# Power.net
KiCad netlist of a schematic drawn in Altium Designer
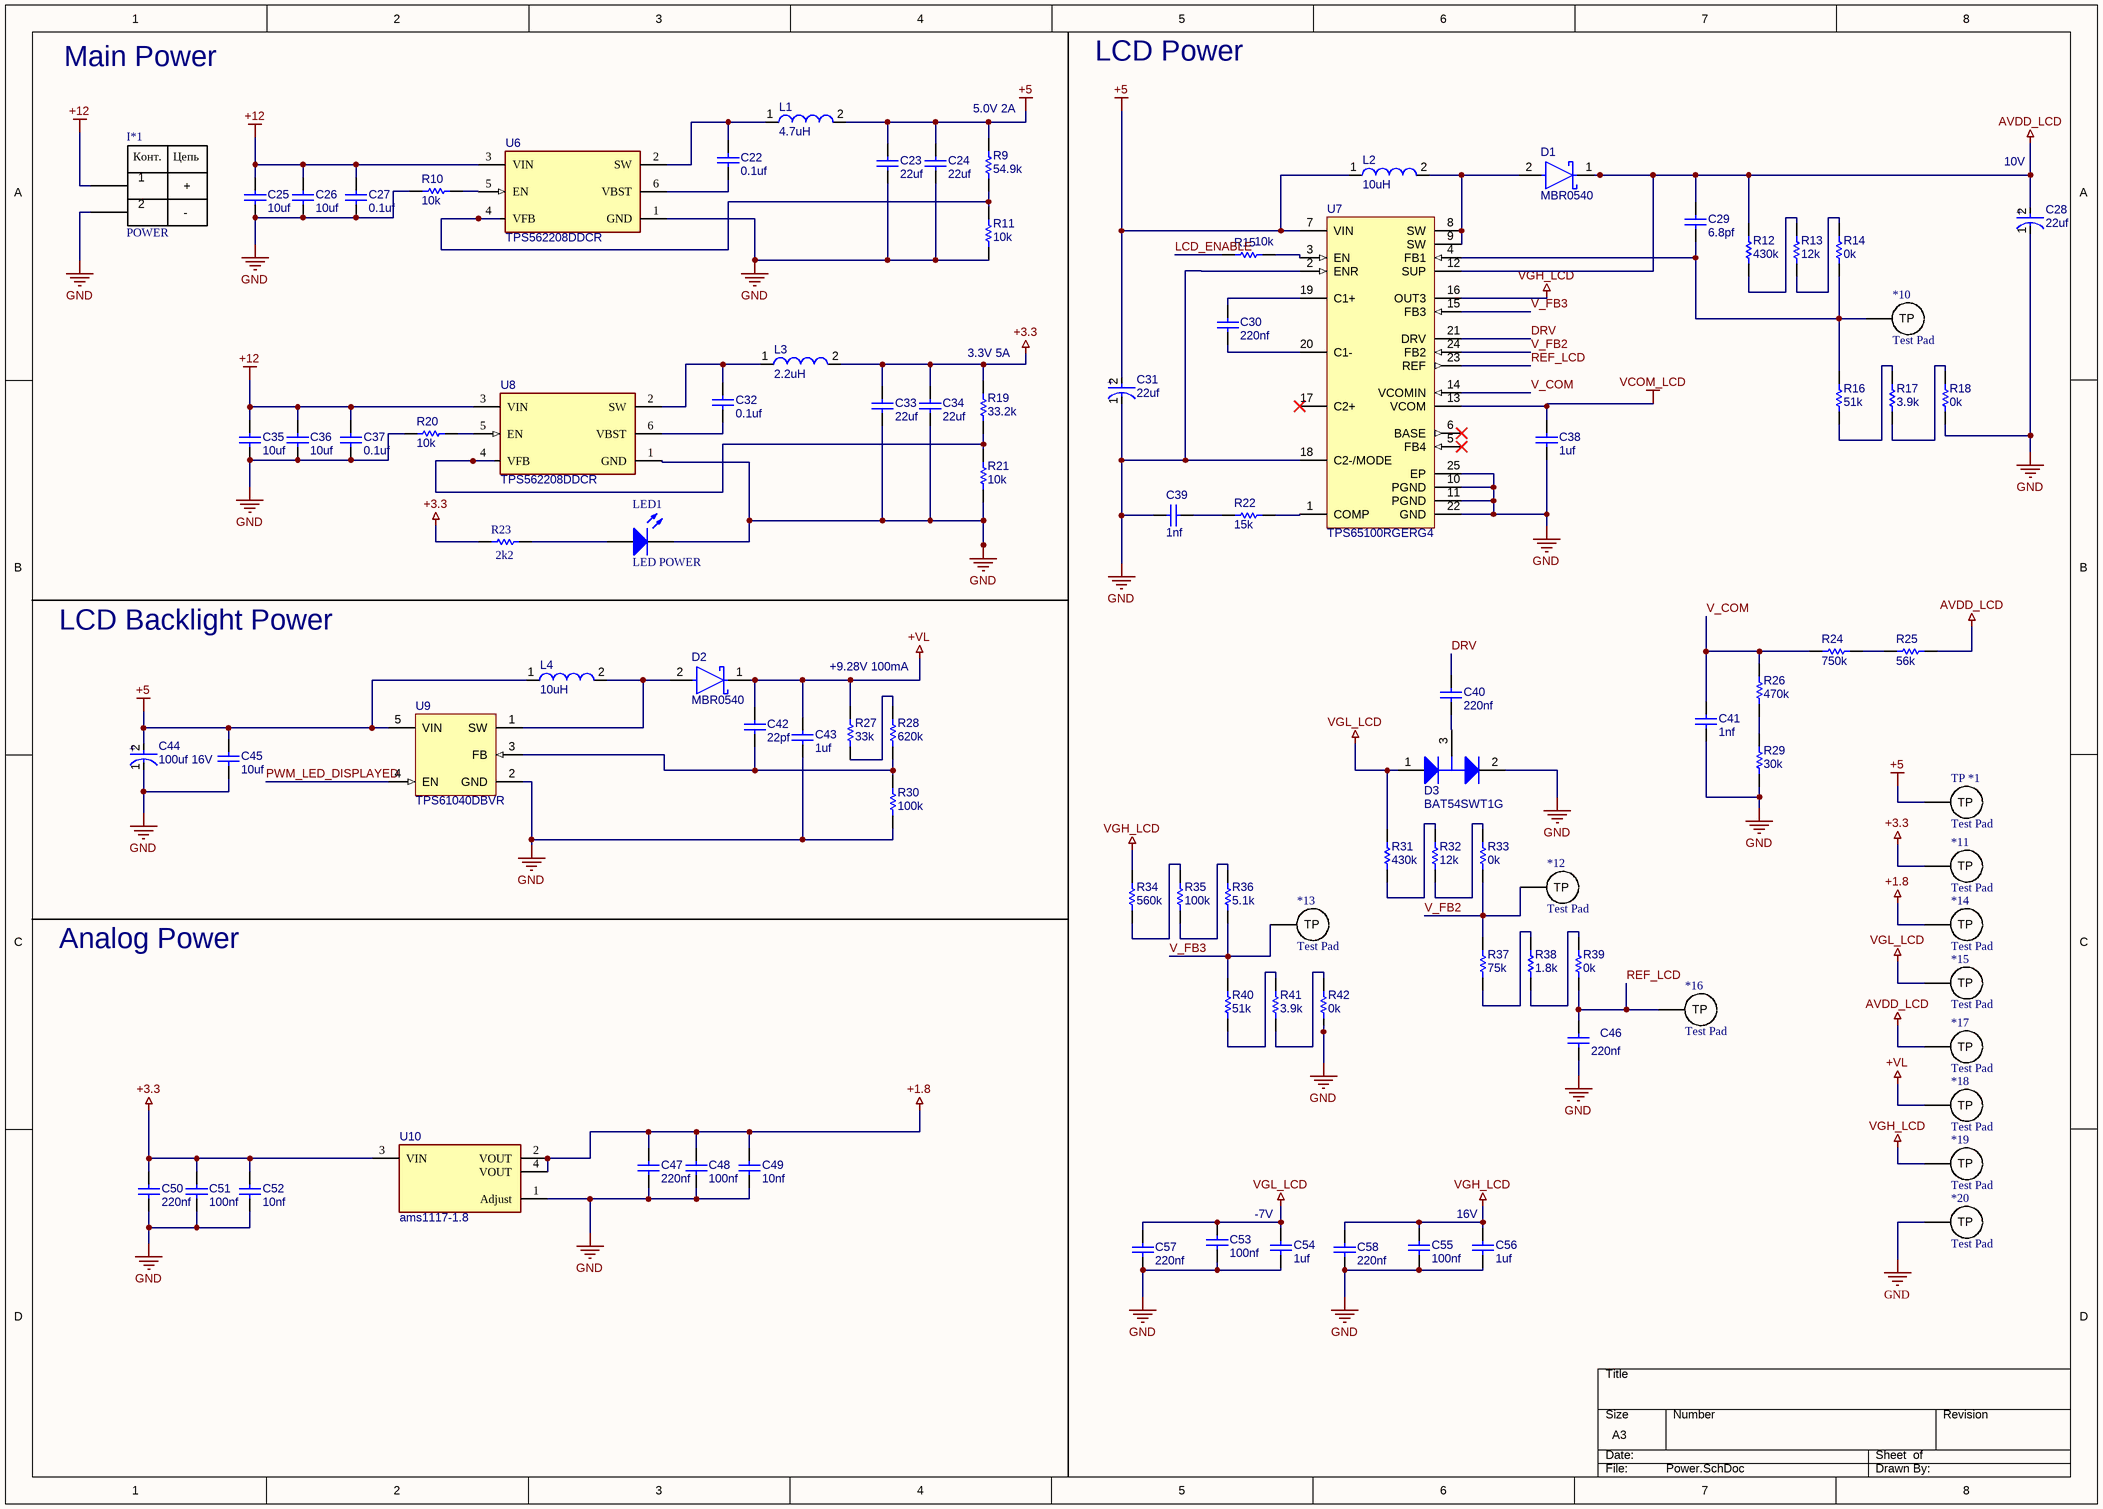
[diagram p0: Power.SchDoc]

(export (version "E")
  (design (tool "Eeschema 10.0.6"))
  (components
    (comp (ref "*10")
      (value "Test Pad")
      (footprint "Test Pad")
      (libsource (lib "Test Pad") (part "Test Pad"))
    )
    (comp (ref "*11")
      (value "Test Pad")
      (footprint "Test Pad")
      (libsource (lib "Test Pad") (part "Test Pad"))
    )
    (comp (ref "*12")
      (value "Test Pad")
      (footprint "Test Pad")
      (libsource (lib "Test Pad") (part "Test Pad"))
    )
    (comp (ref "*13")
      (value "Test Pad")
      (footprint "Test Pad")
      (libsource (lib "Test Pad") (part "Test Pad"))
    )
    (comp (ref "*14")
      (value "Test Pad")
      (footprint "Test Pad")
      (libsource (lib "Test Pad") (part "Test Pad"))
    )
    (comp (ref "*15")
      (value "Test Pad")
      (footprint "Test Pad")
      (libsource (lib "Test Pad") (part "Test Pad"))
    )
    (comp (ref "*16")
      (value "Test Pad")
      (footprint "Test Pad")
      (libsource (lib "Test Pad") (part "Test Pad"))
    )
    (comp (ref "*17")
      (value "Test Pad")
      (footprint "Test Pad")
      (libsource (lib "Test Pad") (part "Test Pad"))
    )
    (comp (ref "*18")
      (value "Test Pad")
      (footprint "Test Pad")
      (libsource (lib "Test Pad") (part "Test Pad"))
    )
    (comp (ref "*19")
      (value "Test Pad")
      (footprint "Test Pad")
      (libsource (lib "Test Pad") (part "Test Pad"))
    )
    (comp (ref "*20")
      (value "Test Pad")
      (footprint "Test Pad")
      (libsource (lib "Test Pad") (part "Test Pad"))
    )
    (comp (ref "C22")
      (value "0.1uf")
      (footprint "CAPC2013X70X45NL10T25")
      (fields (field (name "PART NUMBER") "GRM216R61E105KA12D") (field (name "MANUFACTURER") "Murata"))
      (libsource (lib "Altium Content Vault") (part "CAP"))
    )
    (comp (ref "C23")
      (value "22uf")
      (footprint "CAPC2013X70X45NL10T25")
      (fields (field (name "PART NUMBER") "GRM216R61E105KA12D") (field (name "MANUFACTURER") "Murata"))
      (libsource (lib "Altium Content Vault") (part "CAP"))
    )
    (comp (ref "C24")
      (value "22uf")
      (footprint "CAPC2013X70X45NL10T25")
      (fields (field (name "PART NUMBER") "GRM216R61E105KA12D") (field (name "MANUFACTURER") "Murata"))
      (libsource (lib "Altium Content Vault") (part "CAP"))
    )
    (comp (ref "C25")
      (value "10uf")
      (footprint "CAPC2013X70X45NL10T25")
      (fields (field (name "PART NUMBER") "GRM216R61E105KA12D") (field (name "MANUFACTURER") "Murata"))
      (libsource (lib "Altium Content Vault") (part "CAP"))
    )
    (comp (ref "C26")
      (value "10uf")
      (footprint "CAPC2013X70X45NL10T25")
      (fields (field (name "PART NUMBER") "GRM216R61E105KA12D") (field (name "MANUFACTURER") "Murata"))
      (libsource (lib "Altium Content Vault") (part "CAP"))
    )
    (comp (ref "C27")
      (value "0.1uf")
      (footprint "CAPC2013X70X45NL10T25")
      (fields (field (name "PART NUMBER") "GRM216R61E105KA12D") (field (name "MANUFACTURER") "Murata"))
      (libsource (lib "Altium Content Vault") (part "CAP"))
    )
    (comp (ref "C28")
      (value "22uf")
      (footprint "FP-TAJD-MFG")
      (description "22uF 16V  ±20% 1.1Ω 2917  SMD Tantalum Capacitor")
      (fields (field (name "TOLERANCE") "20%"))
      (libsource (lib "Altium Content Vault") (part "a00bbbee19879c290e62620ae7e47b1"))
    )
    (comp (ref "C29")
      (value "6.8pf")
      (footprint "CAPC2013X70X45NL10T25")
      (fields (field (name "PART NUMBER") "GRM216R61E105KA12D") (field (name "MANUFACTURER") "Murata"))
      (libsource (lib "Altium Content Vault") (part "CAP"))
    )
    (comp (ref "C30")
      (value "220nf")
      (footprint "CAPC2013X70X45NL10T25")
      (fields (field (name "PART NUMBER") "GRM216R61E105KA12D") (field (name "MANUFACTURER") "Murata"))
      (libsource (lib "Altium Content Vault") (part "CAP"))
    )
    (comp (ref "C31")
      (value "22uf")
      (footprint "FP-TAJD-MFG")
      (description "22uF 16V  ±20% 1.1Ω 2917  SMD Tantalum Capacitor")
      (fields (field (name "TOLERANCE") "20%"))
      (libsource (lib "Altium Content Vault") (part "a00bbbee19879c290e62620ae7e47b1"))
    )
    (comp (ref "C32")
      (value "0.1uf")
      (footprint "CAPC2013X70X45NL10T25")
      (fields (field (name "PART NUMBER") "GRM216R61E105KA12D") (field (name "MANUFACTURER") "Murata"))
      (libsource (lib "Altium Content Vault") (part "CAP"))
    )
    (comp (ref "C33")
      (value "22uf")
      (footprint "CAPC2013X70X45NL10T25")
      (fields (field (name "PART NUMBER") "GRM216R61E105KA12D") (field (name "MANUFACTURER") "Murata"))
      (libsource (lib "Altium Content Vault") (part "CAP"))
    )
    (comp (ref "C34")
      (value "22uf")
      (footprint "CAPC2013X70X45NL10T25")
      (fields (field (name "PART NUMBER") "GRM216R61E105KA12D") (field (name "MANUFACTURER") "Murata"))
      (libsource (lib "Altium Content Vault") (part "CAP"))
    )
    (comp (ref "C35")
      (value "10uf")
      (footprint "CAPC2013X70X45NL10T25")
      (fields (field (name "PART NUMBER") "GRM216R61E105KA12D") (field (name "MANUFACTURER") "Murata"))
      (libsource (lib "Altium Content Vault") (part "CAP"))
    )
    (comp (ref "C36")
      (value "10uf")
      (footprint "CAPC2013X70X45NL10T25")
      (fields (field (name "PART NUMBER") "GRM216R61E105KA12D") (field (name "MANUFACTURER") "Murata"))
      (libsource (lib "Altium Content Vault") (part "CAP"))
    )
    (comp (ref "C37")
      (value "0.1uf")
      (footprint "CAPC2013X70X45NL10T25")
      (fields (field (name "PART NUMBER") "GRM216R61E105KA12D") (field (name "MANUFACTURER") "Murata"))
      (libsource (lib "Altium Content Vault") (part "CAP"))
    )
    (comp (ref "C38")
      (value "1uf")
      (footprint "CAPC2013X70X45NL10T25")
      (fields (field (name "PART NUMBER") "GRM216R61E105KA12D") (field (name "MANUFACTURER") "Murata"))
      (libsource (lib "Altium Content Vault") (part "CAP"))
    )
    (comp (ref "C39")
      (value "1nf")
      (footprint "CAPC2013X70X45NL10T25")
      (fields (field (name "PART NUMBER") "GRM216R61E105KA12D") (field (name "MANUFACTURER") "Murata"))
      (libsource (lib "Altium Content Vault") (part "CAP"))
    )
    (comp (ref "C40")
      (value "220nf")
      (footprint "CAPC2013X70X45NL10T25")
      (fields (field (name "PART NUMBER") "GRM216R61E105KA12D") (field (name "MANUFACTURER") "Murata"))
      (libsource (lib "Altium Content Vault") (part "CAP"))
    )
    (comp (ref "C41")
      (value "1nf")
      (footprint "CAPC2013X70X45NL10T25")
      (fields (field (name "PART NUMBER") "GRM216R61E105KA12D") (field (name "MANUFACTURER") "Murata"))
      (libsource (lib "Altium Content Vault") (part "CAP"))
    )
    (comp (ref "C42")
      (value "22pf")
      (footprint "CAPC2013X70X45NL10T25")
      (fields (field (name "PART NUMBER") "GRM216R61E105KA12D") (field (name "MANUFACTURER") "Murata"))
      (libsource (lib "Altium Content Vault") (part "CAP"))
    )
    (comp (ref "C43")
      (value "1uf")
      (footprint "CAPC2013X70X45NL10T25")
      (fields (field (name "PART NUMBER") "GRM216R61E105KA12D") (field (name "MANUFACTURER") "Murata"))
      (libsource (lib "Altium Content Vault") (part "CAP"))
    )
    (comp (ref "C44")
      (value "100uf 16V")
      (footprint "FP-T491D107K016AT-MFG")
      (description "CAP TANT 100UF 10% 16V 2917")
      (fields (field (name "TOLERANCE") "10%") (field (name "VOLTAGE") "16V"))
      (libsource (lib "Altium Content Vault") (part "cf48714ba7e38822c1575c7ec0b6d1f"))
    )
    (comp (ref "C45")
      (value "10uf")
      (footprint "CAPC2013X70X45NL10T25")
      (fields (field (name "PART NUMBER") "GRM216R61E105KA12D") (field (name "MANUFACTURER") "Murata"))
      (libsource (lib "Altium Content Vault") (part "CAP"))
    )
    (comp (ref "C46")
      (value "220nf")
      (footprint "CAPC2013X70X45NL10T25")
      (fields (field (name "PART NUMBER") "GRM216R61E105KA12D") (field (name "MANUFACTURER") "Murata"))
      (libsource (lib "Altium Content Vault") (part "CAP"))
    )
    (comp (ref "C47")
      (value "220nf")
      (footprint "CAPC2013X70X45NL10T25")
      (fields (field (name "PART NUMBER") "GRM216R61E105KA12D") (field (name "MANUFACTURER") "Murata"))
      (libsource (lib "Altium Content Vault") (part "CAP"))
    )
    (comp (ref "C48")
      (value "100nf")
      (footprint "CAPC2013X70X45NL10T25")
      (fields (field (name "PART NUMBER") "GRM216R61E105KA12D") (field (name "MANUFACTURER") "Murata"))
      (libsource (lib "Altium Content Vault") (part "CAP"))
    )
    (comp (ref "C49")
      (value "10nf")
      (footprint "CAPC2013X70X45NL10T25")
      (fields (field (name "PART NUMBER") "GRM216R61E105KA12D") (field (name "MANUFACTURER") "Murata"))
      (libsource (lib "Altium Content Vault") (part "CAP"))
    )
    (comp (ref "C50")
      (value "220nf")
      (footprint "CAPC2013X70X45NL10T25")
      (fields (field (name "PART NUMBER") "GRM216R61E105KA12D") (field (name "MANUFACTURER") "Murata"))
      (libsource (lib "Altium Content Vault") (part "CAP"))
    )
    (comp (ref "C51")
      (value "100nf")
      (footprint "CAPC2013X70X45NL10T25")
      (fields (field (name "PART NUMBER") "GRM216R61E105KA12D") (field (name "MANUFACTURER") "Murata"))
      (libsource (lib "Altium Content Vault") (part "CAP"))
    )
    (comp (ref "C52")
      (value "10nf")
      (footprint "CAPC2013X70X45NL10T25")
      (fields (field (name "PART NUMBER") "GRM216R61E105KA12D") (field (name "MANUFACTURER") "Murata"))
      (libsource (lib "Altium Content Vault") (part "CAP"))
    )
    (comp (ref "C53")
      (value "100nf")
      (footprint "CAPC2013X70X45NL10T25")
      (fields (field (name "PART NUMBER") "GRM216R61E105KA12D") (field (name "MANUFACTURER") "Murata"))
      (libsource (lib "Altium Content Vault") (part "CAP"))
    )
    (comp (ref "C54")
      (value "1uf")
      (footprint "CAPC2013X70X45NL10T25")
      (fields (field (name "PART NUMBER") "GRM216R61E105KA12D") (field (name "MANUFACTURER") "Murata"))
      (libsource (lib "Altium Content Vault") (part "CAP"))
    )
    (comp (ref "C55")
      (value "100nf")
      (footprint "CAPC2013X70X45NL10T25")
      (fields (field (name "PART NUMBER") "GRM216R61E105KA12D") (field (name "MANUFACTURER") "Murata"))
      (libsource (lib "Altium Content Vault") (part "CAP"))
    )
    (comp (ref "C56")
      (value "1uf")
      (footprint "CAPC2013X70X45NL10T25")
      (fields (field (name "PART NUMBER") "GRM216R61E105KA12D") (field (name "MANUFACTURER") "Murata"))
      (libsource (lib "Altium Content Vault") (part "CAP"))
    )
    (comp (ref "C57")
      (value "220nf")
      (footprint "CAPC2013X70X45NL10T25")
      (fields (field (name "PART NUMBER") "GRM216R61E105KA12D") (field (name "MANUFACTURER") "Murata"))
      (libsource (lib "Altium Content Vault") (part "CAP"))
    )
    (comp (ref "C58")
      (value "220nf")
      (footprint "CAPC2013X70X45NL10T25")
      (fields (field (name "PART NUMBER") "GRM216R61E105KA12D") (field (name "MANUFACTURER") "Murata"))
      (libsource (lib "Altium Content Vault") (part "CAP"))
    )
    (comp (ref "D1")
      (value "MBR0540")
      (footprint "FP-425-04-MFG")
      (description "DIODE SCHOTTKY 40V 500MA SOD123")
      (libsource (lib "Altium Content Vault") (part "1d6ec82d83fb6aee721767c19dac4b9"))
    )
    (comp (ref "D2")
      (value "MBR0540")
      (footprint "FP-425-04-MFG")
      (description "DIODE SCHOTTKY 40V 500MA SOD123")
      (libsource (lib "Altium Content Vault") (part "1d6ec82d83fb6aee721767c19dac4b9"))
    )
    (comp (ref "D3")
      (value "BAT54SWT1G")
      (footprint "ONSC-SOT-323-3-419-04_V")
      (description "Dual Series Schottky Barrier Diodes, 3-Pin SOT-323, Pb-Free, Tape and Reel")
      (fields (field (name "MANUFACTURER") "On Semiconductor"))
      (libsource (lib "Altium Content Vault") (part "ONSC-D-A1K2C3-3"))
    )
    (comp (ref "I*1") (value "POWER") (footprint "POWER") (libsource (lib "POWER") (part "POWER")))
    (comp (ref "L1")
      (value "4.7uH")
      (footprint "WE-TPC-4818-M")
      (description "SMD Shielded Tiny Power Inductor WE-TPC, L = 3.90 µH")
      (libsource (lib "Altium Content Vault") (part "PAS-IND-INDUCTOR-2"))
    )
    (comp (ref "L2")
      (value "10uH")
      (footprint "WE-PD2-S")
      (description "SMD Power Inductor WE-PD2, L = 10.0 µH")
      (libsource (lib "Altium Content Vault") (part "PAS-IND-INDUCTOR-2"))
    )
    (comp (ref "L3")
      (value "2.2uH")
      (footprint "WE-TPC-4818-M")
      (description "SMD Shielded Tiny Power Inductor WE-TPC, L = 3.90 µH")
      (libsource (lib "Altium Content Vault") (part "PAS-IND-INDUCTOR-2"))
    )
    (comp (ref "L4")
      (value "10uH")
      (footprint "WE-TPC-4818-M")
      (description "SMD Shielded Tiny Power Inductor WE-TPC, L = 3.90 µH")
      (libsource (lib "Altium Content Vault") (part "PAS-IND-INDUCTOR-2"))
    )
    (comp (ref "LED1")
      (value "LED POWER")
      (footprint "0805_A")
      (description "SMD mono-color Chip LED, WL-SMCW, Red")
      (fields (field (name "PARTNUMBER") "150080RS75000") (field (name "MANUFACTURER") "Wuerth Elektronik"))
      (libsource (lib "Altium Content Vault") (part "WE-LED_K1A2-2"))
    )
    (comp (ref "R9")
      (value "54.9k")
      (footprint "RESC2013X60X35ML10T20")
      (description "Chip Resistor, 1 KOhm, +/- 1%, 125 mW, -55 to 155 degC, 0805 (2012 Metric), RoHS, Tape and Reel")
      (fields (field (name "TOLERANCE") "1%") (field (name "MANUFACTURER") "Yageo"))
      (libsource (lib "Altium Content Vault") (part "RES-2"))
    )
    (comp (ref "R10")
      (value "10k")
      (footprint "RESC2013X60X35ML10T20")
      (description "Chip Resistor, 1 KOhm, +/- 1%, 125 mW, -55 to 155 degC, 0805 (2012 Metric), RoHS, Tape and Reel")
      (fields (field (name "TOLERANCE") "1%") (field (name "MANUFACTURER") "Yageo"))
      (libsource (lib "Altium Content Vault") (part "RES-2"))
    )
    (comp (ref "R11")
      (value "10k")
      (footprint "RESC2013X60X35ML10T20")
      (description "Chip Resistor, 1 KOhm, +/- 1%, 125 mW, -55 to 155 degC, 0805 (2012 Metric), RoHS, Tape and Reel")
      (fields (field (name "TOLERANCE") "1%") (field (name "MANUFACTURER") "Yageo"))
      (libsource (lib "Altium Content Vault") (part "RES-2"))
    )
    (comp (ref "R12")
      (value "430k")
      (footprint "RESC2013X60X35ML10T20")
      (description "Chip Resistor, 1 KOhm, +/- 1%, 125 mW, -55 to 155 degC, 0805 (2012 Metric), RoHS, Tape and Reel")
      (fields (field (name "TOLERANCE") "1%") (field (name "MANUFACTURER") "Yageo"))
      (libsource (lib "Altium Content Vault") (part "RES-2"))
    )
    (comp (ref "R13")
      (value "12k")
      (footprint "RESC2013X60X35ML10T20")
      (description "Chip Resistor, 1 KOhm, +/- 1%, 125 mW, -55 to 155 degC, 0805 (2012 Metric), RoHS, Tape and Reel")
      (fields (field (name "TOLERANCE") "1%") (field (name "MANUFACTURER") "Yageo"))
      (libsource (lib "Altium Content Vault") (part "RES-2"))
    )
    (comp (ref "R14")
      (value "0k")
      (footprint "RESC2013X60X35ML10T20")
      (description "Chip Resistor, 1 KOhm, +/- 1%, 125 mW, -55 to 155 degC, 0805 (2012 Metric), RoHS, Tape and Reel")
      (fields (field (name "TOLERANCE") "1%") (field (name "MANUFACTURER") "Yageo"))
      (libsource (lib "Altium Content Vault") (part "RES-2"))
    )
    (comp (ref "R15")
      (value "10k")
      (footprint "RESC2013X60X35ML10T20")
      (description "Chip Resistor, 1 KOhm, +/- 1%, 125 mW, -55 to 155 degC, 0805 (2012 Metric), RoHS, Tape and Reel")
      (fields (field (name "TOLERANCE") "1%") (field (name "MANUFACTURER") "Yageo"))
      (libsource (lib "Altium Content Vault") (part "RES-2"))
    )
    (comp (ref "R16")
      (value "51k")
      (footprint "RESC2013X60X35ML10T20")
      (description "Chip Resistor, 1 KOhm, +/- 1%, 125 mW, -55 to 155 degC, 0805 (2012 Metric), RoHS, Tape and Reel")
      (fields (field (name "TOLERANCE") "1%") (field (name "MANUFACTURER") "Yageo"))
      (libsource (lib "Altium Content Vault") (part "RES-2"))
    )
    (comp (ref "R17")
      (value "3.9k")
      (footprint "RESC2013X60X35ML10T20")
      (description "Chip Resistor, 1 KOhm, +/- 1%, 125 mW, -55 to 155 degC, 0805 (2012 Metric), RoHS, Tape and Reel")
      (fields (field (name "TOLERANCE") "1%") (field (name "MANUFACTURER") "Yageo"))
      (libsource (lib "Altium Content Vault") (part "RES-2"))
    )
    (comp (ref "R18")
      (value "0k")
      (footprint "RESC2013X60X35ML10T20")
      (description "Chip Resistor, 1 KOhm, +/- 1%, 125 mW, -55 to 155 degC, 0805 (2012 Metric), RoHS, Tape and Reel")
      (fields (field (name "TOLERANCE") "1%") (field (name "MANUFACTURER") "Yageo"))
      (libsource (lib "Altium Content Vault") (part "RES-2"))
    )
    (comp (ref "R19")
      (value "33.2k")
      (footprint "RESC2013X60X35ML10T20")
      (description "Chip Resistor, 1 KOhm, +/- 1%, 125 mW, -55 to 155 degC, 0805 (2012 Metric), RoHS, Tape and Reel")
      (fields (field (name "TOLERANCE") "1%") (field (name "MANUFACTURER") "Yageo"))
      (libsource (lib "Altium Content Vault") (part "RES-2"))
    )
    (comp (ref "R20")
      (value "10k")
      (footprint "RESC2013X60X35ML10T20")
      (description "Chip Resistor, 1 KOhm, +/- 1%, 125 mW, -55 to 155 degC, 0805 (2012 Metric), RoHS, Tape and Reel")
      (fields (field (name "TOLERANCE") "1%") (field (name "MANUFACTURER") "Yageo"))
      (libsource (lib "Altium Content Vault") (part "RES-2"))
    )
    (comp (ref "R21")
      (value "10k")
      (footprint "RESC2013X60X35ML10T20")
      (description "Chip Resistor, 1 KOhm, +/- 1%, 125 mW, -55 to 155 degC, 0805 (2012 Metric), RoHS, Tape and Reel")
      (fields (field (name "TOLERANCE") "1%") (field (name "MANUFACTURER") "Yageo"))
      (libsource (lib "Altium Content Vault") (part "RES-2"))
    )
    (comp (ref "R22")
      (value "15k")
      (footprint "RESC2013X60X35ML10T20")
      (description "Chip Resistor, 1 KOhm, +/- 1%, 125 mW, -55 to 155 degC, 0805 (2012 Metric), RoHS, Tape and Reel")
      (fields (field (name "TOLERANCE") "1%") (field (name "MANUFACTURER") "Yageo"))
      (libsource (lib "Altium Content Vault") (part "RES-2"))
    )
    (comp (ref "R23")
      (value "2k2")
      (footprint "RESC1608X50X30NL20T20")
      (fields (field (name "PART NUMBER") "RR0816P-753-B-T5") (field (name "MANUFACTURER") "Susumu"))
      (libsource (lib "Altium Content Vault") (part "RES"))
    )
    (comp (ref "R24")
      (value "750k")
      (footprint "RESC2013X60X35ML10T20")
      (description "Chip Resistor, 1 KOhm, +/- 1%, 125 mW, -55 to 155 degC, 0805 (2012 Metric), RoHS, Tape and Reel")
      (fields (field (name "TOLERANCE") "1%") (field (name "MANUFACTURER") "Yageo"))
      (libsource (lib "Altium Content Vault") (part "RES-2"))
    )
    (comp (ref "R25")
      (value "56k")
      (footprint "RESC2013X60X35ML10T20")
      (description "Chip Resistor, 1 KOhm, +/- 1%, 125 mW, -55 to 155 degC, 0805 (2012 Metric), RoHS, Tape and Reel")
      (fields (field (name "TOLERANCE") "1%") (field (name "MANUFACTURER") "Yageo"))
      (libsource (lib "Altium Content Vault") (part "RES-2"))
    )
    (comp (ref "R26")
      (value "470k")
      (footprint "RESC2013X60X35ML10T20")
      (description "Chip Resistor, 1 KOhm, +/- 1%, 125 mW, -55 to 155 degC, 0805 (2012 Metric), RoHS, Tape and Reel")
      (fields (field (name "TOLERANCE") "1%") (field (name "MANUFACTURER") "Yageo"))
      (libsource (lib "Altium Content Vault") (part "RES-2"))
    )
    (comp (ref "R27")
      (value "33k")
      (footprint "RESC2013X60X35ML10T20")
      (description "Chip Resistor, 1 KOhm, +/- 1%, 125 mW, -55 to 155 degC, 0805 (2012 Metric), RoHS, Tape and Reel")
      (fields (field (name "TOLERANCE") "1%") (field (name "MANUFACTURER") "Yageo"))
      (libsource (lib "Altium Content Vault") (part "RES-2"))
    )
    (comp (ref "R28")
      (value "620k")
      (footprint "RESC2013X60X35ML10T20")
      (description "Chip Resistor, 1 KOhm, +/- 1%, 125 mW, -55 to 155 degC, 0805 (2012 Metric), RoHS, Tape and Reel")
      (fields (field (name "TOLERANCE") "1%") (field (name "MANUFACTURER") "Yageo"))
      (libsource (lib "Altium Content Vault") (part "RES-2"))
    )
    (comp (ref "R29")
      (value "30k")
      (footprint "RESC2013X60X35ML10T20")
      (description "Chip Resistor, 1 KOhm, +/- 1%, 125 mW, -55 to 155 degC, 0805 (2012 Metric), RoHS, Tape and Reel")
      (fields (field (name "TOLERANCE") "1%") (field (name "MANUFACTURER") "Yageo"))
      (libsource (lib "Altium Content Vault") (part "RES-2"))
    )
    (comp (ref "R30")
      (value "100k")
      (footprint "RESC2013X60X35ML10T20")
      (description "Chip Resistor, 1 KOhm, +/- 1%, 125 mW, -55 to 155 degC, 0805 (2012 Metric), RoHS, Tape and Reel")
      (fields (field (name "TOLERANCE") "1%") (field (name "MANUFACTURER") "Yageo"))
      (libsource (lib "Altium Content Vault") (part "RES-2"))
    )
    (comp (ref "R31")
      (value "430k")
      (footprint "RESC2013X60X35ML10T20")
      (description "Chip Resistor, 1 KOhm, +/- 1%, 125 mW, -55 to 155 degC, 0805 (2012 Metric), RoHS, Tape and Reel")
      (fields (field (name "TOLERANCE") "1%") (field (name "MANUFACTURER") "Yageo"))
      (libsource (lib "Altium Content Vault") (part "RES-2"))
    )
    (comp (ref "R32")
      (value "12k")
      (footprint "RESC2013X60X35ML10T20")
      (description "Chip Resistor, 1 KOhm, +/- 1%, 125 mW, -55 to 155 degC, 0805 (2012 Metric), RoHS, Tape and Reel")
      (fields (field (name "TOLERANCE") "1%") (field (name "MANUFACTURER") "Yageo"))
      (libsource (lib "Altium Content Vault") (part "RES-2"))
    )
    (comp (ref "R33")
      (value "0k")
      (footprint "RESC2013X60X35ML10T20")
      (description "Chip Resistor, 1 KOhm, +/- 1%, 125 mW, -55 to 155 degC, 0805 (2012 Metric), RoHS, Tape and Reel")
      (fields (field (name "TOLERANCE") "1%") (field (name "MANUFACTURER") "Yageo"))
      (libsource (lib "Altium Content Vault") (part "RES-2"))
    )
    (comp (ref "R34")
      (value "560k")
      (footprint "RESC2013X60X35ML10T20")
      (description "Chip Resistor, 1 KOhm, +/- 1%, 125 mW, -55 to 155 degC, 0805 (2012 Metric), RoHS, Tape and Reel")
      (fields (field (name "TOLERANCE") "1%") (field (name "MANUFACTURER") "Yageo"))
      (libsource (lib "Altium Content Vault") (part "RES-2"))
    )
    (comp (ref "R35")
      (value "100k")
      (footprint "RESC2013X60X35ML10T20")
      (description "Chip Resistor, 1 KOhm, +/- 1%, 125 mW, -55 to 155 degC, 0805 (2012 Metric), RoHS, Tape and Reel")
      (fields (field (name "TOLERANCE") "1%") (field (name "MANUFACTURER") "Yageo"))
      (libsource (lib "Altium Content Vault") (part "RES-2"))
    )
    (comp (ref "R36")
      (value "5.1k")
      (footprint "RESC2013X60X35ML10T20")
      (description "Chip Resistor, 1 KOhm, +/- 1%, 125 mW, -55 to 155 degC, 0805 (2012 Metric), RoHS, Tape and Reel")
      (fields (field (name "TOLERANCE") "1%") (field (name "MANUFACTURER") "Yageo"))
      (libsource (lib "Altium Content Vault") (part "RES-2"))
    )
    (comp (ref "R37")
      (value "75k")
      (footprint "RESC2013X60X35ML10T20")
      (description "Chip Resistor, 1 KOhm, +/- 1%, 125 mW, -55 to 155 degC, 0805 (2012 Metric), RoHS, Tape and Reel")
      (fields (field (name "TOLERANCE") "1%") (field (name "MANUFACTURER") "Yageo"))
      (libsource (lib "Altium Content Vault") (part "RES-2"))
    )
    (comp (ref "R38")
      (value "1.8k")
      (footprint "RESC2013X60X35ML10T20")
      (description "Chip Resistor, 1 KOhm, +/- 1%, 125 mW, -55 to 155 degC, 0805 (2012 Metric), RoHS, Tape and Reel")
      (fields (field (name "TOLERANCE") "1%") (field (name "MANUFACTURER") "Yageo"))
      (libsource (lib "Altium Content Vault") (part "RES-2"))
    )
    (comp (ref "R39")
      (value "0k")
      (footprint "RESC2013X60X35ML10T20")
      (description "Chip Resistor, 1 KOhm, +/- 1%, 125 mW, -55 to 155 degC, 0805 (2012 Metric), RoHS, Tape and Reel")
      (fields (field (name "TOLERANCE") "1%") (field (name "MANUFACTURER") "Yageo"))
      (libsource (lib "Altium Content Vault") (part "RES-2"))
    )
    (comp (ref "R40")
      (value "51k")
      (footprint "RESC2013X60X35ML10T20")
      (description "Chip Resistor, 1 KOhm, +/- 1%, 125 mW, -55 to 155 degC, 0805 (2012 Metric), RoHS, Tape and Reel")
      (fields (field (name "TOLERANCE") "1%") (field (name "MANUFACTURER") "Yageo"))
      (libsource (lib "Altium Content Vault") (part "RES-2"))
    )
    (comp (ref "R41")
      (value "3.9k")
      (footprint "RESC2013X60X35ML10T20")
      (description "Chip Resistor, 1 KOhm, +/- 1%, 125 mW, -55 to 155 degC, 0805 (2012 Metric), RoHS, Tape and Reel")
      (fields (field (name "TOLERANCE") "1%") (field (name "MANUFACTURER") "Yageo"))
      (libsource (lib "Altium Content Vault") (part "RES-2"))
    )
    (comp (ref "R42")
      (value "0k")
      (footprint "RESC2013X60X35ML10T20")
      (description "Chip Resistor, 1 KOhm, +/- 1%, 125 mW, -55 to 155 degC, 0805 (2012 Metric), RoHS, Tape and Reel")
      (fields (field (name "TOLERANCE") "1%") (field (name "MANUFACTURER") "Yageo"))
      (libsource (lib "Altium Content Vault") (part "RES-2"))
    )
    (comp (ref "TP *1")
      (value "Test Pad")
      (footprint "Test Pad")
      (libsource (lib "Test Pad") (part "Test Pad"))
    )
    (comp (ref "U6")
      (value "TPS562208DDCR")
      (footprint "FP-DDC0006A-IPC_A")
      (description "IC REG BUCK ADJ 2A TSOT23-6")
      (libsource (lib "Altium Content Vault") (part "31d0a13bcb823f7fa58c78a9b473f81"))
    )
    (comp (ref "U7")
      (value "TPS65100RGERG4")
      (footprint "TI-RGE24-2450X2450TP_V")
      (fields (field (name "MANUFACTURER") "Texas Instruments"))
      (libsource (lib "Altium Content Vault") (part "TI-TPS6510XRGE24-2450X2450TP"))
    )
    (comp (ref "U8")
      (value "TPS562208DDCR")
      (footprint "FP-DDC0006A-IPC_A")
      (description "IC REG BUCK ADJ 2A TSOT23-6")
      (libsource (lib "Altium Content Vault") (part "31d0a13bcb823f7fa58c78a9b473f81"))
    )
    (comp (ref "U9")
      (value "TPS61040DBVR")
      (footprint "DBV0005A_N")
      (fields (field (name "MANUFACTURER") "Texas Instruments"))
      (libsource (lib "Altium Content Vault") (part "TI-TPS61040DBV5"))
    )
    (comp (ref "U10")
      (value "ams1117-1.8")
      (footprint "FP-ams1117-IPC_C")
      (description "1A LOW DROPOUT VOLTAGE REGULATOR")
      (libsource (lib "Altium Content Vault") (part "59ad430b93a2c51b3e6ee7c3b069677"))
    )
  )
  (nets
    (net (code "1") (name "+1.8") (class "Default")
      (node (ref "*14") (pin "1") (pinfunction "TP_1") (pintype "passive"))
      (node (ref "C47") (pin "2") (pinfunction "2_2") (pintype "passive"))
      (node (ref "C48") (pin "2") (pinfunction "2_2") (pintype "passive"))
      (node (ref "C49") (pin "2") (pinfunction "2_2") (pintype "passive"))
      (node (ref "U10") (pin "2") (pinfunction "VOUT_2") (pintype "passive"))
      (node (ref "U10") (pin "4") (pinfunction "VOUT_4") (pintype "passive"))
    )
    (net (code "2") (name "+3.3") (class "Default")
      (node (ref "*11") (pin "1") (pinfunction "TP_1") (pintype "passive"))
      (node (ref "C33") (pin "2") (pinfunction "2_2") (pintype "passive"))
      (node (ref "C34") (pin "2") (pinfunction "2_2") (pintype "passive"))
      (node (ref "C50") (pin "2") (pinfunction "2_2") (pintype "passive"))
      (node (ref "C51") (pin "2") (pinfunction "2_2") (pintype "passive"))
      (node (ref "C52") (pin "2") (pinfunction "2_2") (pintype "passive"))
      (node (ref "L3") (pin "2") (pinfunction "2_2") (pintype "passive"))
      (node (ref "R19") (pin "2") (pinfunction "2_2") (pintype "passive"))
      (node (ref "R23") (pin "1") (pinfunction "1_1") (pintype "passive"))
      (node (ref "U10") (pin "3") (pinfunction "VIN_3") (pintype "power_in"))
    )
    (net (code "3") (name "+5") (class "Default")
      (node (ref "C23") (pin "2") (pinfunction "2_2") (pintype "passive"))
      (node (ref "C24") (pin "2") (pinfunction "2_2") (pintype "passive"))
      (node (ref "C31") (pin "2") (pinfunction "A_2") (pintype "passive"))
      (node (ref "C44") (pin "2") (pinfunction "A_2") (pintype "passive"))
      (node (ref "C45") (pin "2") (pinfunction "2_2") (pintype "passive"))
      (node (ref "L1") (pin "2") (pinfunction "2_2") (pintype "passive"))
      (node (ref "L2") (pin "1") (pinfunction "1_1") (pintype "passive"))
      (node (ref "L4") (pin "1") (pinfunction "1_1") (pintype "passive"))
      (node (ref "R9") (pin "2") (pinfunction "2_2") (pintype "passive"))
      (node (ref "TP *1") (pin "1") (pinfunction "TP_1") (pintype "passive"))
      (node (ref "U7") (pin "7") (pinfunction "VIN_7") (pintype "power_in"))
      (node (ref "U9") (pin "5") (pinfunction "VIN_5") (pintype "power_in"))
    )
    (net (code "4") (name "+12") (class "Default")
      (node (ref "C25") (pin "2") (pinfunction "2_2") (pintype "passive"))
      (node (ref "C26") (pin "2") (pinfunction "2_2") (pintype "passive"))
      (node (ref "C27") (pin "2") (pinfunction "2_2") (pintype "passive"))
      (node (ref "C35") (pin "2") (pinfunction "2_2") (pintype "passive"))
      (node (ref "C36") (pin "2") (pinfunction "2_2") (pintype "passive"))
      (node (ref "C37") (pin "2") (pinfunction "2_2") (pintype "passive"))
      (node (ref "I*1") (pin "1") (pinfunction "+_1") (pintype "power_in"))
      (node (ref "U6") (pin "3") (pinfunction "VIN_3") (pintype "power_in"))
      (node (ref "U8") (pin "3") (pinfunction "VIN_3") (pintype "power_in"))
    )
    (net (code "5") (name "+VL") (class "Default")
      (node (ref "*18") (pin "1") (pinfunction "TP_1") (pintype "passive"))
      (node (ref "C42") (pin "2") (pinfunction "2_2") (pintype "passive"))
      (node (ref "C43") (pin "2") (pinfunction "2_2") (pintype "passive"))
      (node (ref "D2") (pin "1") (pinfunction "C_1") (pintype "passive"))
      (node (ref "R27") (pin "2") (pinfunction "2_2") (pintype "passive"))
    )
    (net (code "6") (name "/DRV") (class "Default")
      (node (ref "C40") (pin "2") (pinfunction "2_2") (pintype "passive"))
      (node (ref "U7") (pin "21") (pinfunction "DRV_21") (pintype "power_in"))
    )
    (net (code "7") (name "/LCD_ENABLE") (class "Default")
      (node (ref "R15") (pin "2") (pinfunction "2_2") (pintype "passive"))
    )
    (net (code "8") (name "/PWM_LED_DISPLAYED") (class "Default")
      (node (ref "U9") (pin "4") (pinfunction "EN_4") (pintype "input"))
    )
    (net (code "9") (name "/REF_LCD") (class "Default")
      (node (ref "*16") (pin "1") (pinfunction "TP_1") (pintype "passive"))
      (node (ref "C46") (pin "2") (pinfunction "2_2") (pintype "passive"))
      (node (ref "R39") (pin "1") (pinfunction "1_1") (pintype "passive"))
      (node (ref "U7") (pin "23") (pinfunction "REF_23") (pintype "output"))
    )
    (net (code "10") (name "/V_COM") (class "Default")
      (node (ref "C41") (pin "2") (pinfunction "2_2") (pintype "passive"))
      (node (ref "R24") (pin "2") (pinfunction "2_2") (pintype "passive"))
      (node (ref "R26") (pin "2") (pinfunction "2_2") (pintype "passive"))
      (node (ref "U7") (pin "14") (pinfunction "VCOMIN_14") (pintype "input"))
    )
    (net (code "11") (name "/V_FB2") (class "Default")
      (node (ref "*12") (pin "1") (pinfunction "TP_1") (pintype "passive"))
      (node (ref "R33") (pin "1") (pinfunction "1_1") (pintype "passive"))
      (node (ref "R37") (pin "2") (pinfunction "2_2") (pintype "passive"))
      (node (ref "U7") (pin "24") (pinfunction "FB2_24") (pintype "input"))
    )
    (net (code "12") (name "/V_FB3") (class "Default")
      (node (ref "*13") (pin "1") (pinfunction "TP_1") (pintype "passive"))
      (node (ref "R36") (pin "1") (pinfunction "1_1") (pintype "passive"))
      (node (ref "R40") (pin "2") (pinfunction "2_2") (pintype "passive"))
      (node (ref "U7") (pin "15") (pinfunction "FB3_15") (pintype "input"))
    )
    (net (code "13") (name "AVDD_LCD") (class "Default")
      (node (ref "*17") (pin "1") (pinfunction "TP_1") (pintype "passive"))
      (node (ref "C28") (pin "2") (pinfunction "A_2") (pintype "passive"))
      (node (ref "C29") (pin "2") (pinfunction "2_2") (pintype "passive"))
      (node (ref "D1") (pin "1") (pinfunction "C_1") (pintype "passive"))
      (node (ref "R12") (pin "2") (pinfunction "2_2") (pintype "passive"))
      (node (ref "R25") (pin "1") (pinfunction "1_1") (pintype "passive"))
      (node (ref "U7") (pin "12") (pinfunction "SUP_12") (pintype "power_in"))
    )
    (net (code "14") (name "GND") (class "Default")
      (node (ref "*20") (pin "1") (pinfunction "TP_1") (pintype "passive"))
      (node (ref "C23") (pin "1") (pinfunction "1_1") (pintype "passive"))
      (node (ref "C24") (pin "1") (pinfunction "1_1") (pintype "passive"))
      (node (ref "C25") (pin "1") (pinfunction "1_1") (pintype "passive"))
      (node (ref "C26") (pin "1") (pinfunction "1_1") (pintype "passive"))
      (node (ref "C27") (pin "1") (pinfunction "1_1") (pintype "passive"))
      (node (ref "C28") (pin "1") (pinfunction "C_1") (pintype "passive"))
      (node (ref "C31") (pin "1") (pinfunction "C_1") (pintype "passive"))
      (node (ref "C33") (pin "1") (pinfunction "1_1") (pintype "passive"))
      (node (ref "C34") (pin "1") (pinfunction "1_1") (pintype "passive"))
      (node (ref "C35") (pin "1") (pinfunction "1_1") (pintype "passive"))
      (node (ref "C36") (pin "1") (pinfunction "1_1") (pintype "passive"))
      (node (ref "C37") (pin "1") (pinfunction "1_1") (pintype "passive"))
      (node (ref "C38") (pin "1") (pinfunction "1_1") (pintype "passive"))
      (node (ref "C39") (pin "2") (pinfunction "2_2") (pintype "passive"))
      (node (ref "C41") (pin "1") (pinfunction "1_1") (pintype "passive"))
      (node (ref "C43") (pin "1") (pinfunction "1_1") (pintype "passive"))
      (node (ref "C44") (pin "1") (pinfunction "C_1") (pintype "passive"))
      (node (ref "C45") (pin "1") (pinfunction "1_1") (pintype "passive"))
      (node (ref "C46") (pin "1") (pinfunction "1_1") (pintype "passive"))
      (node (ref "C47") (pin "1") (pinfunction "1_1") (pintype "passive"))
      (node (ref "C48") (pin "1") (pinfunction "1_1") (pintype "passive"))
      (node (ref "C49") (pin "1") (pinfunction "1_1") (pintype "passive"))
      (node (ref "C50") (pin "1") (pinfunction "1_1") (pintype "passive"))
      (node (ref "C51") (pin "1") (pinfunction "1_1") (pintype "passive"))
      (node (ref "C52") (pin "1") (pinfunction "1_1") (pintype "passive"))
      (node (ref "C53") (pin "1") (pinfunction "1_1") (pintype "passive"))
      (node (ref "C54") (pin "1") (pinfunction "1_1") (pintype "passive"))
      (node (ref "C55") (pin "1") (pinfunction "1_1") (pintype "passive"))
      (node (ref "C56") (pin "1") (pinfunction "1_1") (pintype "passive"))
      (node (ref "C57") (pin "1") (pinfunction "1_1") (pintype "passive"))
      (node (ref "C58") (pin "1") (pinfunction "1_1") (pintype "passive"))
      (node (ref "D3") (pin "2") (pinfunction "K_2") (pintype "passive"))
      (node (ref "I*1") (pin "2") (pinfunction "-_2") (pintype "power_in"))
      (node (ref "LED1") (pin "1") (pinfunction "K_1") (pintype "passive"))
      (node (ref "R10") (pin "1") (pinfunction "1_1") (pintype "passive"))
      (node (ref "R11") (pin "1") (pinfunction "1_1") (pintype "passive"))
      (node (ref "R18") (pin "1") (pinfunction "1_1") (pintype "passive"))
      (node (ref "R20") (pin "1") (pinfunction "1_1") (pintype "passive"))
      (node (ref "R21") (pin "1") (pinfunction "1_1") (pintype "passive"))
      (node (ref "R29") (pin "1") (pinfunction "1_1") (pintype "passive"))
      (node (ref "R30") (pin "1") (pinfunction "1_1") (pintype "passive"))
      (node (ref "R42") (pin "1") (pinfunction "1_1") (pintype "passive"))
      (node (ref "U10") (pin "1") (pinfunction "Adjust_1") (pintype "passive"))
      (node (ref "U6") (pin "1") (pinfunction "GND_1") (pintype "power_in"))
      (node (ref "U7") (pin "10") (pinfunction "PGND_10") (pintype "power_in"))
      (node (ref "U7") (pin "11") (pinfunction "PGND_11") (pintype "power_in"))
      (node (ref "U7") (pin "18") (pinfunction "C2-/MODE_18") (pintype "passive"))
      (node (ref "U7") (pin "2") (pinfunction "ENR_2") (pintype "input"))
      (node (ref "U7") (pin "22") (pinfunction "GND_22") (pintype "power_in"))
      (node (ref "U7") (pin "25") (pinfunction "EP_25") (pintype "power_in"))
      (node (ref "U8") (pin "1") (pinfunction "GND_1") (pintype "power_in"))
      (node (ref "U9") (pin "2") (pinfunction "GND_2") (pintype "power_in"))
    )
    (net (code "15") (name "Net-(*10-TP)") (class "Default")
      (node (ref "*10") (pin "1") (pinfunction "TP_1") (pintype "passive"))
      (node (ref "C29") (pin "1") (pinfunction "1_1") (pintype "passive"))
      (node (ref "R14") (pin "1") (pinfunction "1_1") (pintype "passive"))
      (node (ref "R16") (pin "2") (pinfunction "2_2") (pintype "passive"))
      (node (ref "U7") (pin "4") (pinfunction "FB1_4") (pintype "input"))
    )
    (net (code "16") (name "Net-(C39-Pad1)") (class "Default")
      (node (ref "C39") (pin "1") (pinfunction "1_1") (pintype "passive"))
      (node (ref "R22") (pin "2") (pinfunction "2_2") (pintype "passive"))
    )
    (net (code "17") (name "Net-(D1-A)") (class "Default")
      (node (ref "D1") (pin "2") (pinfunction "A_2") (pintype "passive"))
      (node (ref "L2") (pin "2") (pinfunction "2_2") (pintype "passive"))
      (node (ref "U7") (pin "8") (pinfunction "SW_8") (pintype "power_in"))
      (node (ref "U7") (pin "9") (pinfunction "SW_9") (pintype "power_in"))
    )
    (net (code "18") (name "Net-(D2-A)") (class "Default")
      (node (ref "D2") (pin "2") (pinfunction "A_2") (pintype "passive"))
      (node (ref "L4") (pin "2") (pinfunction "2_2") (pintype "passive"))
      (node (ref "U9") (pin "1") (pinfunction "SW_1") (pintype "power_in"))
    )
    (net (code "19") (name "Net-(D3-K{slash}A)") (class "Default")
      (node (ref "C40") (pin "1") (pinfunction "1_1") (pintype "passive"))
      (node (ref "D3") (pin "3") (pinfunction "K/A_3") (pintype "passive"))
    )
    (net (code "20") (name "Net-(LED1-A)") (class "Default")
      (node (ref "LED1") (pin "2") (pinfunction "A_2") (pintype "passive"))
      (node (ref "R23") (pin "2") (pinfunction "2_2") (pintype "passive"))
    )
    (net (code "21") (name "Net-(R12-Pad1)") (class "Default")
      (node (ref "R12") (pin "1") (pinfunction "1_1") (pintype "passive"))
      (node (ref "R13") (pin "2") (pinfunction "2_2") (pintype "passive"))
    )
    (net (code "22") (name "Net-(R13-Pad1)") (class "Default")
      (node (ref "R13") (pin "1") (pinfunction "1_1") (pintype "passive"))
      (node (ref "R14") (pin "2") (pinfunction "2_2") (pintype "passive"))
    )
    (net (code "23") (name "Net-(R16-Pad1)") (class "Default")
      (node (ref "R16") (pin "1") (pinfunction "1_1") (pintype "passive"))
      (node (ref "R17") (pin "2") (pinfunction "2_2") (pintype "passive"))
    )
    (net (code "24") (name "Net-(R17-Pad1)") (class "Default")
      (node (ref "R17") (pin "1") (pinfunction "1_1") (pintype "passive"))
      (node (ref "R18") (pin "2") (pinfunction "2_2") (pintype "passive"))
    )
    (net (code "25") (name "Net-(R24-Pad1)") (class "Default")
      (node (ref "R24") (pin "1") (pinfunction "1_1") (pintype "passive"))
      (node (ref "R25") (pin "2") (pinfunction "2_2") (pintype "passive"))
    )
    (net (code "26") (name "Net-(R26-Pad1)") (class "Default")
      (node (ref "R26") (pin "1") (pinfunction "1_1") (pintype "passive"))
      (node (ref "R29") (pin "2") (pinfunction "2_2") (pintype "passive"))
    )
    (net (code "27") (name "Net-(R27-Pad1)") (class "Default")
      (node (ref "R27") (pin "1") (pinfunction "1_1") (pintype "passive"))
      (node (ref "R28") (pin "2") (pinfunction "2_2") (pintype "passive"))
    )
    (net (code "28") (name "Net-(R31-Pad1)") (class "Default")
      (node (ref "R31") (pin "1") (pinfunction "1_1") (pintype "passive"))
      (node (ref "R32") (pin "2") (pinfunction "2_2") (pintype "passive"))
    )
    (net (code "29") (name "Net-(R32-Pad1)") (class "Default")
      (node (ref "R32") (pin "1") (pinfunction "1_1") (pintype "passive"))
      (node (ref "R33") (pin "2") (pinfunction "2_2") (pintype "passive"))
    )
    (net (code "30") (name "Net-(R34-Pad1)") (class "Default")
      (node (ref "R34") (pin "1") (pinfunction "1_1") (pintype "passive"))
      (node (ref "R35") (pin "2") (pinfunction "2_2") (pintype "passive"))
    )
    (net (code "31") (name "Net-(R35-Pad1)") (class "Default")
      (node (ref "R35") (pin "1") (pinfunction "1_1") (pintype "passive"))
      (node (ref "R36") (pin "2") (pinfunction "2_2") (pintype "passive"))
    )
    (net (code "32") (name "Net-(R37-Pad1)") (class "Default")
      (node (ref "R37") (pin "1") (pinfunction "1_1") (pintype "passive"))
      (node (ref "R38") (pin "2") (pinfunction "2_2") (pintype "passive"))
    )
    (net (code "33") (name "Net-(R38-Pad1)") (class "Default")
      (node (ref "R38") (pin "1") (pinfunction "1_1") (pintype "passive"))
      (node (ref "R39") (pin "2") (pinfunction "2_2") (pintype "passive"))
    )
    (net (code "34") (name "Net-(R40-Pad1)") (class "Default")
      (node (ref "R40") (pin "1") (pinfunction "1_1") (pintype "passive"))
      (node (ref "R41") (pin "2") (pinfunction "2_2") (pintype "passive"))
    )
    (net (code "35") (name "Net-(R41-Pad1)") (class "Default")
      (node (ref "R41") (pin "1") (pinfunction "1_1") (pintype "passive"))
      (node (ref "R42") (pin "2") (pinfunction "2_2") (pintype "passive"))
    )
    (net (code "36") (name "Net-(U6-EN)") (class "Default")
      (node (ref "R10") (pin "2") (pinfunction "2_2") (pintype "passive"))
      (node (ref "U6") (pin "5") (pinfunction "EN_5") (pintype "input"))
    )
    (net (code "37") (name "Net-(U6-SW)") (class "Default")
      (node (ref "C22") (pin "2") (pinfunction "2_2") (pintype "passive"))
      (node (ref "L1") (pin "1") (pinfunction "1_1") (pintype "passive"))
      (node (ref "U6") (pin "2") (pinfunction "SW_2") (pintype "passive"))
    )
    (net (code "38") (name "Net-(U6-VBST)") (class "Default")
      (node (ref "C22") (pin "1") (pinfunction "1_1") (pintype "passive"))
      (node (ref "U6") (pin "6") (pinfunction "VBST_6") (pintype "passive"))
    )
    (net (code "39") (name "Net-(U6-VFB)") (class "Default")
      (node (ref "R11") (pin "2") (pinfunction "2_2") (pintype "passive"))
      (node (ref "R9") (pin "1") (pinfunction "1_1") (pintype "passive"))
      (node (ref "U6") (pin "4") (pinfunction "VFB_4") (pintype "passive"))
    )
    (net (code "40") (name "Net-(U7-C1+)") (class "Default")
      (node (ref "C30") (pin "2") (pinfunction "2_2") (pintype "passive"))
      (node (ref "U7") (pin "19") (pinfunction "C1+_19") (pintype "passive"))
    )
    (net (code "41") (name "Net-(U7-C1-)") (class "Default")
      (node (ref "C30") (pin "1") (pinfunction "1_1") (pintype "passive"))
      (node (ref "U7") (pin "20") (pinfunction "C1-_20") (pintype "passive"))
    )
    (net (code "42") (name "Net-(U7-COMP)") (class "Default")
      (node (ref "R22") (pin "1") (pinfunction "1_1") (pintype "passive"))
      (node (ref "U7") (pin "1") (pinfunction "COMP_1") (pintype "passive"))
    )
    (net (code "43") (name "Net-(U7-EN)") (class "Default")
      (node (ref "R15") (pin "1") (pinfunction "1_1") (pintype "passive"))
      (node (ref "U7") (pin "3") (pinfunction "EN_3") (pintype "input"))
    )
    (net (code "44") (name "Net-(U8-EN)") (class "Default")
      (node (ref "R20") (pin "2") (pinfunction "2_2") (pintype "passive"))
      (node (ref "U8") (pin "5") (pinfunction "EN_5") (pintype "input"))
    )
    (net (code "45") (name "Net-(U8-SW)") (class "Default")
      (node (ref "C32") (pin "2") (pinfunction "2_2") (pintype "passive"))
      (node (ref "L3") (pin "1") (pinfunction "1_1") (pintype "passive"))
      (node (ref "U8") (pin "2") (pinfunction "SW_2") (pintype "passive"))
    )
    (net (code "46") (name "Net-(U8-VBST)") (class "Default")
      (node (ref "C32") (pin "1") (pinfunction "1_1") (pintype "passive"))
      (node (ref "U8") (pin "6") (pinfunction "VBST_6") (pintype "passive"))
    )
    (net (code "47") (name "Net-(U8-VFB)") (class "Default")
      (node (ref "R19") (pin "1") (pinfunction "1_1") (pintype "passive"))
      (node (ref "R21") (pin "2") (pinfunction "2_2") (pintype "passive"))
      (node (ref "U8") (pin "4") (pinfunction "VFB_4") (pintype "passive"))
    )
    (net (code "48") (name "Net-(U9-FB)") (class "Default")
      (node (ref "C42") (pin "1") (pinfunction "1_1") (pintype "passive"))
      (node (ref "R28") (pin "1") (pinfunction "1_1") (pintype "passive"))
      (node (ref "R30") (pin "2") (pinfunction "2_2") (pintype "passive"))
      (node (ref "U9") (pin "3") (pinfunction "FB_3") (pintype "input"))
    )
    (net (code "49") (name "VCOM_LCD") (class "Default")
      (node (ref "C38") (pin "2") (pinfunction "2_2") (pintype "passive"))
      (node (ref "U7") (pin "13") (pinfunction "VCOM_13") (pintype "power_in"))
    )
    (net (code "50") (name "VGH_LCD") (class "Default")
      (node (ref "*19") (pin "1") (pinfunction "TP_1") (pintype "passive"))
      (node (ref "C55") (pin "2") (pinfunction "2_2") (pintype "passive"))
      (node (ref "C56") (pin "2") (pinfunction "2_2") (pintype "passive"))
      (node (ref "C58") (pin "2") (pinfunction "2_2") (pintype "passive"))
      (node (ref "R34") (pin "2") (pinfunction "2_2") (pintype "passive"))
      (node (ref "U7") (pin "16") (pinfunction "OUT3_16") (pintype "power_in"))
    )
    (net (code "51") (name "VGL_LCD") (class "Default")
      (node (ref "*15") (pin "1") (pinfunction "TP_1") (pintype "passive"))
      (node (ref "C53") (pin "2") (pinfunction "2_2") (pintype "passive"))
      (node (ref "C54") (pin "2") (pinfunction "2_2") (pintype "passive"))
      (node (ref "C57") (pin "2") (pinfunction "2_2") (pintype "passive"))
      (node (ref "D3") (pin "1") (pinfunction "A_1") (pintype "passive"))
      (node (ref "R31") (pin "2") (pinfunction "2_2") (pintype "passive"))
    )
    (net (code "52") (name "unconnected-(U7-BASE-Pad6)") (class "Default")
      (node (ref "U7") (pin "6") (pinfunction "BASE_6") (pintype "output+no_connect"))
    )
    (net (code "53") (name "unconnected-(U7-C2+-Pad17)") (class "Default")
      (node (ref "U7") (pin "17") (pinfunction "C2+_17") (pintype "passive+no_connect"))
    )
    (net (code "54") (name "unconnected-(U7-FB4-Pad5)") (class "Default")
      (node (ref "U7") (pin "5") (pinfunction "FB4_5") (pintype "input+no_connect"))
    )
  )
)
